# MP_MCU.net
KiCad netlist of a schematic drawn in Altium Designer
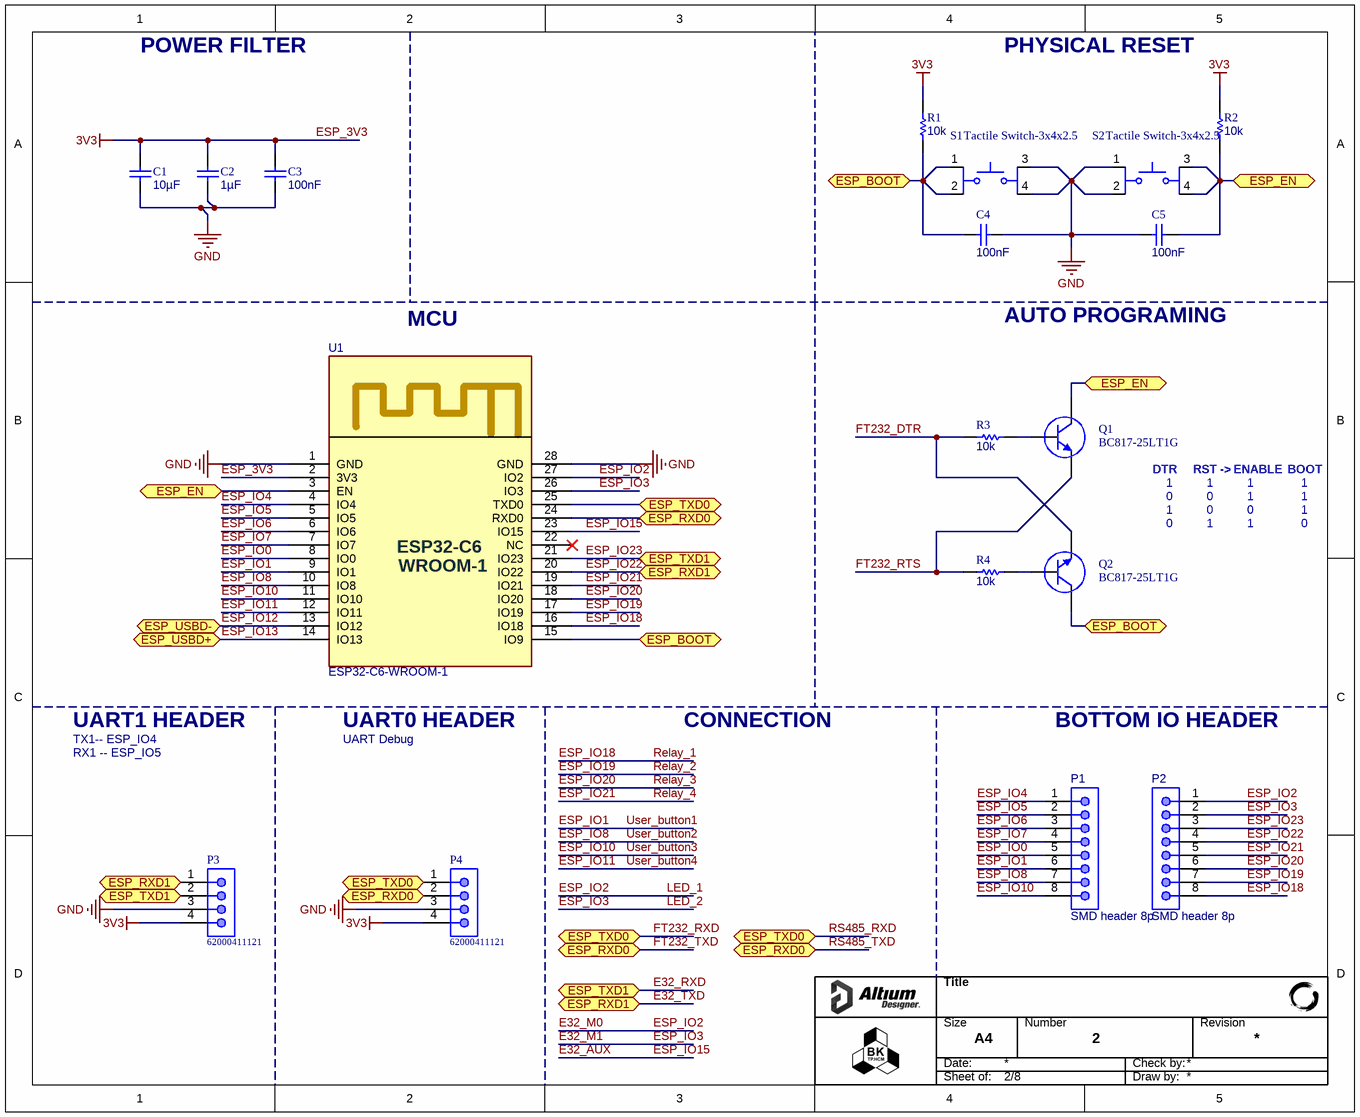
[diagram p0: [MP] MCU.SchDoc]

(export (version "E")
  (design (tool "Eeschema 10.0.6"))
  (components
    (comp (ref "C1")
      (value "10µF")
      (footprint "CAP_0603")
      (description "CAP, size 0603, 10 uF, 10 VDC, 10%")
      (fields
        (field (name "MANUFACTURER") "Samsung Electro-Mechanics")
        (field (name "LCSC PART #") "C19702")
        (field (name "SOURCE") "Capacitor_0603_10_percent.SchLib")
      )
      (libsource (lib "University of Technology") (part "010603475106.3"))
    )
    (comp (ref "C2")
      (value "1µF")
      (footprint "CAP_0603")
      (description "CAP, size 0603, 1 uF, 16 VDC, 10%")
      (fields
        (field (name "MANUFACTURER PART NUMBER") "CL10B105KO8NNWC")
        (field (name "TOLERANCE") "10%")
        (field (name "SOURCE") "Capacitor_0603_10_percent.SchLib")
      )
      (libsource (lib "University of Technology") (part "010603475106.3"))
    )
    (comp (ref "C3")
      (value "100nF")
      (footprint "CAP_0603")
      (description "CAP, size 0603, 100 nF, 50 VDC, 10%")
      (fields
        (field (name "MANUFACTURER PART NUMBER") "CGA3E3X8R1H104K080AE")
        (field (name "LCSC PART #") "C14663")
        (field (name "SOURCE") "Capacitor_0603_10_percent.SchLib")
      )
      (libsource (lib "University of Technology") (part "010603475106.3"))
    )
    (comp (ref "C4")
      (value "100nF")
      (footprint "CAP_0603")
      (description "CAP, size 0603, 100 nF, 50 VDC, 10%")
      (fields
        (field (name "MANUFACTURER PART NUMBER") "CGA3E3X8R1H104K080AE")
        (field (name "LCSC PART #") "C14663")
        (field (name "SOURCE") "Capacitor_0603_10_percent.SchLib")
      )
      (libsource (lib "University of Technology") (part "010603475106.3"))
    )
    (comp (ref "C5")
      (value "100nF")
      (footprint "CAP_0603")
      (description "CAP, size 0603, 100 nF, 50 VDC, 10%")
      (fields
        (field (name "MANUFACTURER PART NUMBER") "CGA3E3X8R1H104K080AE")
        (field (name "LCSC PART #") "C14663")
        (field (name "SOURCE") "Capacitor_0603_10_percent.SchLib")
      )
      (libsource (lib "University of Technology") (part "010603475106.3"))
    )
    (comp (ref "P1")
      (value "SMD header 8p")
      (footprint "SMD header 8p")
      (libsource (lib "University of Technology") (part "SMD header 8p"))
    )
    (comp (ref "P2")
      (value "SMD header 8p")
      (footprint "SMD header 8p")
      (libsource (lib "University of Technology") (part "SMD header 8p"))
    )
    (comp (ref "P3")
      (value "62000411121")
      (footprint "62000411121")
      (description "WR-PHD Pin Header, THT, pitch 2mm, Single Row, Vertical, 4p")
      (fields (field (name "MANUFACTURER") "Wurth Elektronik"))
      (libsource (lib "University of Technology") (part "62000411121"))
    )
    (comp (ref "P4")
      (value "62000411121")
      (footprint "62000411121")
      (description "WR-PHD Pin Header, THT, pitch 2mm, Single Row, Vertical, 4p")
      (fields (field (name "MANUFACTURER") "Wurth Elektronik"))
      (libsource (lib "University of Technology") (part "62000411121"))
    )
    (comp (ref "Q1")
      (value "BC817-25LT1G")
      (footprint "ONSC-SOT-23-3-318-08_V")
      (description "Small Signal Bipolar Transistor, 0.5A I(C), 45V V(BR)CEO, 1-Element, NPN, Silicon, TO-236")
      (libsource (lib "University of Technology") (part "TRANS-NPN-3"))
    )
    (comp (ref "Q2")
      (value "BC817-25LT1G")
      (footprint "ONSC-SOT-23-3-318-08_V")
      (description "Small Signal Bipolar Transistor, 0.5A I(C), 45V V(BR)CEO, 1-Element, NPN, Silicon, TO-236")
      (libsource (lib "University of Technology") (part "TRANS-NPN-3"))
    )
    (comp (ref "R1")
      (value "10k")
      (footprint "RES_0603")
      (description "RES, size 0603, 10 KOhm, 1/10 W, 1%")
      (fields
        (field (name "MANUFACTURER PART NUMBER") "RC0603FR-0710KL")
        (field (name "MANUFACTURER") "YAGEO")
      )
      (libsource (lib "University of Technology") (part "00060371541"))
    )
    (comp (ref "R2")
      (value "10k")
      (footprint "RES_0603")
      (description "RES, size 0603, 10 KOhm, 1/10 W, 1%")
      (fields
        (field (name "MANUFACTURER PART NUMBER") "RC0603FR-0710KL")
        (field (name "MANUFACTURER") "YAGEO")
      )
      (libsource (lib "University of Technology") (part "00060371541"))
    )
    (comp (ref "R3")
      (value "10k")
      (footprint "RES_0603")
      (description "RES, size 0603, 10 KOhm, 1/10 W, 1%")
      (fields
        (field (name "MANUFACTURER PART NUMBER") "RC0603FR-0710KL")
        (field (name "MANUFACTURER") "YAGEO")
      )
      (libsource (lib "University of Technology") (part "00060371541"))
    )
    (comp (ref "R4")
      (value "10k")
      (footprint "RES_0603")
      (description "RES, size 0603, 10 KOhm, 1/10 W, 1%")
      (fields
        (field (name "MANUFACTURER PART NUMBER") "RC0603FR-0710KL")
        (field (name "MANUFACTURER") "YAGEO")
      )
      (libsource (lib "University of Technology") (part "00060371541"))
    )
    (comp (ref "S1")
      (value "Tactile Switch-3x4x2.5")
      (footprint "Tactile Switch-3x4x2.5 Footprint")
      (description "Tactile Switch, 3x4x2.5mm")
      (libsource (lib "University of Technology") (part "Tactile Switch"))
    )
    (comp (ref "S2")
      (value "Tactile Switch-3x4x2.5")
      (footprint "Tactile Switch-3x4x2.5 Footprint")
      (description "Tactile Switch, 3x4x2.5mm")
      (libsource (lib "University of Technology") (part "Tactile Switch"))
    )
    (comp (ref "U1")
      (value "ESP32-C6-WROOM-1")
      (footprint "ESP32-C6-WROOM-1-Footprint")
      (description "Module that supports 2.4 GHz Wi-Fi 6 (802.11ax), Bluetooth® 5 (LE), Zigbee and")
      (libsource (lib "University of Technology") (part "ESP32-C6-WROOM-1"))
    )
  )
  (nets
    (net (code "1") (name "/E32_AUX") (class "Default")
      (node (ref "U1") (pin "23") (pinfunction "IO15_23") (pintype "passive"))
    )
    (net (code "2") (name "/E32_M0") (class "Default")
      (node (ref "P2") (pin "1") (pinfunction "1_1") (pintype "passive"))
      (node (ref "U1") (pin "27") (pinfunction "IO2_27") (pintype "passive"))
    )
    (net (code "3") (name "/E32_M1") (class "Default")
      (node (ref "P2") (pin "2") (pinfunction "2_2") (pintype "passive"))
      (node (ref "U1") (pin "26") (pinfunction "IO3_26") (pintype "passive"))
    )
    (net (code "4") (name "/E32_RXD") (class "Default")
      (node (ref "P2") (pin "3") (pinfunction "3_3") (pintype "passive"))
      (node (ref "P3") (pin "2") (pinfunction "2_2") (pintype "passive"))
      (node (ref "U1") (pin "21") (pinfunction "IO23_21") (pintype "passive"))
    )
    (net (code "5") (name "/E32_TXD") (class "Default")
      (node (ref "P2") (pin "4") (pinfunction "4_4") (pintype "passive"))
      (node (ref "P3") (pin "1") (pinfunction "1_1") (pintype "passive"))
      (node (ref "U1") (pin "20") (pinfunction "IO22_20") (pintype "passive"))
    )
    (net (code "6") (name "/ESP_BOOT") (class "Default")
      (node (ref "C4") (pin "1") (pinfunction "1_1") (pintype "passive"))
      (node (ref "Q2") (pin "3") (pinfunction "C_3") (pintype "passive"))
      (node (ref "R1") (pin "1") (pinfunction "1_1") (pintype "passive"))
      (node (ref "S1") (pin "1") (pinfunction "1_1") (pintype "passive"))
      (node (ref "S1") (pin "2") (pinfunction "2_2") (pintype "passive"))
      (node (ref "U1") (pin "15") (pinfunction "IO9_15") (pintype "passive"))
    )
    (net (code "7") (name "/ESP_EN") (class "Default")
      (node (ref "C5") (pin "2") (pinfunction "2_2") (pintype "passive"))
      (node (ref "Q1") (pin "3") (pinfunction "C_3") (pintype "passive"))
      (node (ref "R2") (pin "1") (pinfunction "1_1") (pintype "passive"))
      (node (ref "S2") (pin "3") (pinfunction "3_3") (pintype "passive"))
      (node (ref "S2") (pin "4") (pinfunction "4_4") (pintype "passive"))
      (node (ref "U1") (pin "3") (pinfunction "EN_3") (pintype "passive"))
    )
    (net (code "8") (name "/ESP_IO0") (class "Default")
      (node (ref "P1") (pin "5") (pinfunction "5_5") (pintype "passive"))
      (node (ref "U1") (pin "8") (pinfunction "IO0_8") (pintype "passive"))
    )
    (net (code "9") (name "/ESP_IO1") (class "Default")
      (node (ref "P1") (pin "6") (pinfunction "6_6") (pintype "passive"))
      (node (ref "U1") (pin "9") (pinfunction "IO1_9") (pintype "passive"))
    )
    (net (code "10") (name "/ESP_IO4") (class "Default")
      (node (ref "P1") (pin "1") (pinfunction "1_1") (pintype "passive"))
      (node (ref "U1") (pin "4") (pinfunction "IO4_4") (pintype "passive"))
    )
    (net (code "11") (name "/ESP_IO5") (class "Default")
      (node (ref "P1") (pin "2") (pinfunction "2_2") (pintype "passive"))
      (node (ref "U1") (pin "5") (pinfunction "IO5_5") (pintype "passive"))
    )
    (net (code "12") (name "/ESP_IO6") (class "Default")
      (node (ref "P1") (pin "3") (pinfunction "3_3") (pintype "passive"))
      (node (ref "U1") (pin "6") (pinfunction "IO6_6") (pintype "passive"))
    )
    (net (code "13") (name "/ESP_IO7") (class "Default")
      (node (ref "P1") (pin "4") (pinfunction "4_4") (pintype "passive"))
      (node (ref "U1") (pin "7") (pinfunction "IO7_7") (pintype "passive"))
    )
    (net (code "14") (name "/ESP_IO8") (class "Default")
      (node (ref "P1") (pin "7") (pinfunction "7_7") (pintype "passive"))
      (node (ref "U1") (pin "10") (pinfunction "IO8_10") (pintype "passive"))
    )
    (net (code "15") (name "/ESP_IO10") (class "Default")
      (node (ref "P1") (pin "8") (pinfunction "8_8") (pintype "passive"))
      (node (ref "U1") (pin "11") (pinfunction "IO10_11") (pintype "passive"))
    )
    (net (code "16") (name "/ESP_IO11") (class "Default")
      (node (ref "U1") (pin "12") (pinfunction "IO11_12") (pintype "passive"))
    )
    (net (code "17") (name "/ESP_IO12") (class "Default")
      (node (ref "U1") (pin "13") (pinfunction "IO12_13") (pintype "passive"))
    )
    (net (code "18") (name "/ESP_IO13") (class "Default")
      (node (ref "U1") (pin "14") (pinfunction "IO13_14") (pintype "passive"))
    )
    (net (code "19") (name "/ESP_IO18") (class "Default")
      (node (ref "P2") (pin "8") (pinfunction "8_8") (pintype "passive"))
      (node (ref "U1") (pin "16") (pinfunction "IO18_16") (pintype "passive"))
    )
    (net (code "20") (name "/ESP_IO19") (class "Default")
      (node (ref "P2") (pin "7") (pinfunction "7_7") (pintype "passive"))
      (node (ref "U1") (pin "17") (pinfunction "IO19_17") (pintype "passive"))
    )
    (net (code "21") (name "/ESP_IO20") (class "Default")
      (node (ref "P2") (pin "6") (pinfunction "6_6") (pintype "passive"))
      (node (ref "U1") (pin "18") (pinfunction "IO20_18") (pintype "passive"))
    )
    (net (code "22") (name "/ESP_IO21") (class "Default")
      (node (ref "P2") (pin "5") (pinfunction "5_5") (pintype "passive"))
      (node (ref "U1") (pin "19") (pinfunction "IO21_19") (pintype "passive"))
    )
    (net (code "23") (name "/FT232_DTR") (class "Default")
      (node (ref "Q2") (pin "2") (pinfunction "E_2") (pintype "passive"))
      (node (ref "R3") (pin "2") (pinfunction "2_2") (pintype "passive"))
    )
    (net (code "24") (name "/FT232_RTS") (class "Default")
      (node (ref "Q1") (pin "2") (pinfunction "E_2") (pintype "passive"))
      (node (ref "R4") (pin "1") (pinfunction "1_1") (pintype "passive"))
    )
    (net (code "25") (name "/FT232_RXD") (class "Default")
      (node (ref "P4") (pin "1") (pinfunction "1_1") (pintype "passive"))
      (node (ref "U1") (pin "25") (pinfunction "TXD0_25") (pintype "passive"))
    )
    (net (code "26") (name "/FT232_TXD") (class "Default")
      (node (ref "P4") (pin "2") (pinfunction "2_2") (pintype "passive"))
      (node (ref "U1") (pin "24") (pinfunction "RXD0_24") (pintype "passive"))
    )
    (net (code "27") (name "3V3") (class "Default")
      (node (ref "C1") (pin "2") (pinfunction "2_2") (pintype "passive"))
      (node (ref "C2") (pin "2") (pinfunction "2_2") (pintype "passive"))
      (node (ref "C3") (pin "2") (pinfunction "2_2") (pintype "passive"))
      (node (ref "P3") (pin "4") (pinfunction "4_4") (pintype "passive"))
      (node (ref "P4") (pin "4") (pinfunction "4_4") (pintype "passive"))
      (node (ref "R1") (pin "2") (pinfunction "2_2") (pintype "passive"))
      (node (ref "R2") (pin "2") (pinfunction "2_2") (pintype "passive"))
      (node (ref "U1") (pin "2") (pinfunction "3V3_2") (pintype "passive"))
    )
    (net (code "28") (name "GND") (class "Default")
      (node (ref "C1") (pin "1") (pinfunction "1_1") (pintype "passive"))
      (node (ref "C2") (pin "1") (pinfunction "1_1") (pintype "passive"))
      (node (ref "C3") (pin "1") (pinfunction "1_1") (pintype "passive"))
      (node (ref "C4") (pin "2") (pinfunction "2_2") (pintype "passive"))
      (node (ref "C5") (pin "1") (pinfunction "1_1") (pintype "passive"))
      (node (ref "P3") (pin "3") (pinfunction "3_3") (pintype "passive"))
      (node (ref "P4") (pin "3") (pinfunction "3_3") (pintype "passive"))
      (node (ref "S1") (pin "3") (pinfunction "3_3") (pintype "passive"))
      (node (ref "S1") (pin "4") (pinfunction "4_4") (pintype "passive"))
      (node (ref "S2") (pin "1") (pinfunction "1_1") (pintype "passive"))
      (node (ref "S2") (pin "2") (pinfunction "2_2") (pintype "passive"))
      (node (ref "U1") (pin "1") (pinfunction "GND_1") (pintype "passive"))
      (node (ref "U1") (pin "28") (pinfunction "GND_28") (pintype "passive"))
    )
    (net (code "29") (name "Net-(Q1-B)") (class "Default")
      (node (ref "Q1") (pin "1") (pinfunction "B_1") (pintype "passive"))
      (node (ref "R3") (pin "1") (pinfunction "1_1") (pintype "passive"))
    )
    (net (code "30") (name "Net-(Q2-B)") (class "Default")
      (node (ref "Q2") (pin "1") (pinfunction "B_1") (pintype "passive"))
      (node (ref "R4") (pin "2") (pinfunction "2_2") (pintype "passive"))
    )
    (net (code "31") (name "unconnected-(U1-NC-Pad22)") (class "Default")
      (node (ref "U1") (pin "22") (pinfunction "NC_22") (pintype "passive+no_connect"))
    )
  )
)
